# BatteryVCsmooth.net
KiCad netlist of a schematic drawn in Altium Designer
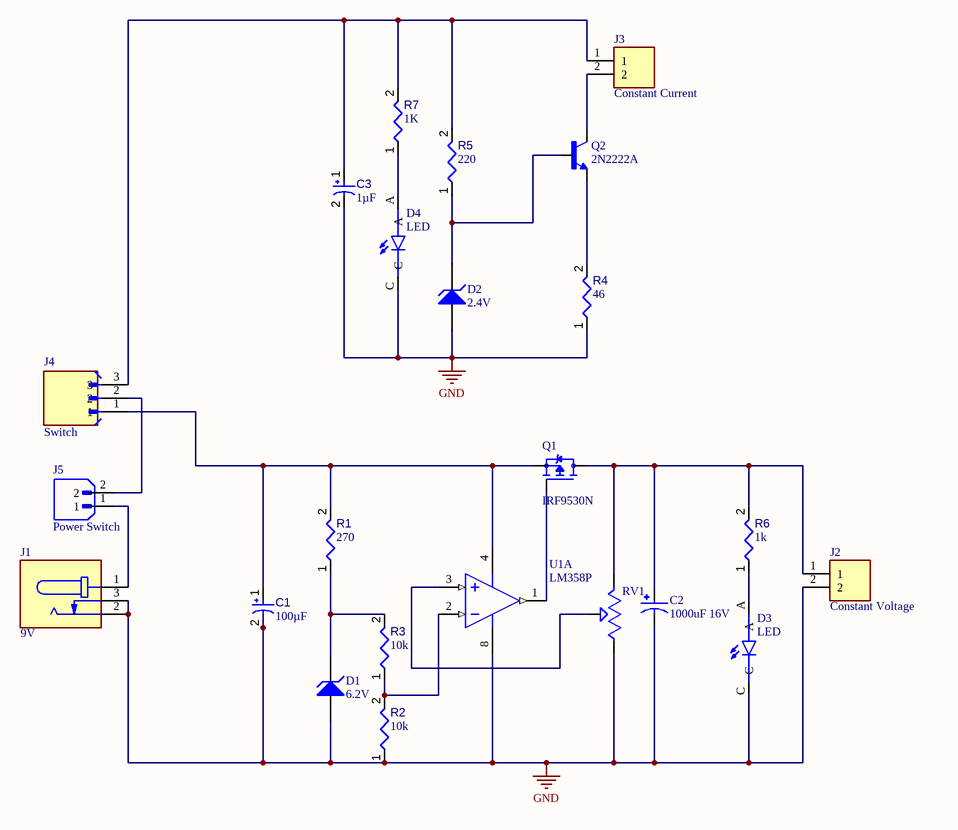
[diagram p0: BatteryVCsmooth.SchDoc]

(export (version "E")
  (design (tool "Eeschema 10.0.6"))
  (components
    (comp (ref "C1")
      (value "100µF")
      (footprint "CAPPR65-350-1150X800X1250")
      (description "Aluminum Electrolytic Capacitor, 100 uF, +/- 20%, 50 V, -40 to 85 degC, 2-Pin THD, RoHS, Bulk")
      (fields (field (name "MANUFACTURER") "Panasonic") (field (name "TOLERANCE") "20%"))
      (libsource (lib "GuardianCall") (part "CAP-P-2"))
    )
    (comp (ref "C2")
      (value "1000uF 16V")
      (footprint "CAPPRD500W60D1000H2000")
      (description "1000F 16V Aluminum Electrolytic Capacitors Radial, Can 10000 Hrs @ 105C")
      (fields (field (name "MP") "EEU-EB1C102B") (field (name "MF") "Panasonic"))
      (libsource (lib "1000uf_16V") (part "EEUEB1C102B"))
    )
    (comp (ref "C3")
      (value "1µF")
      (footprint "CAPPR55-200-1100X500X1200")
      (description "Aluminum Electrolytic Capacitor, 1 uF, +/- 20%, 50 V, -55 to 105 degC, 2-Pin THD, RoHS, Bulk")
      (fields (field (name "TOLERANCE") "20%") (field (name "MANUFACTURER") "Panasonic"))
      (libsource (lib "GuardianCall") (part "CAP-P-2"))
    )
    (comp (ref "D1")
      (value "6.2V")
      (footprint "FAIR-DO-35-2")
      (description "Zener Diode, 6.1 V, 5 mA, -65 to 200 degC, 2-Pin DO-35, RoHS, Bulk")
      (fields (field (name "MANUFACTURER") "Fairchild Semiconductor") (field (name "TOLERANCE") "6%"))
      (libsource (lib "GuardianCall") (part "DZEN-AK-2"))
    )
    (comp (ref "D2")
      (value "2.4V")
      (footprint "FAIR-DO-35-2")
      (description "Zener Diode, 2.4 V, 5 mA, -65 to 200 degC, 2-Pin DO-35, RoHS, Bulk")
      (fields (field (name "MANUFACTURER") "Fairchild Semiconductor") (field (name "TOLERANCE") "6%"))
      (libsource (lib "GuardianCall") (part "DZEN-AK-2"))
    )
    (comp (ref "D3")
      (value "LED")
      (footprint "LED_WP7113ID")
      (description "Red 617nm LED Indication - Discrete 2V Radial")
      (fields (field (name "MP") "WP7113ID") (field (name "MF") "Kingbright"))
      (libsource (lib "RedLED") (part "WP7113ID"))
    )
    (comp (ref "D4")
      (value "LED")
      (footprint "LED_WP7113ID")
      (description "Red 617nm LED Indication - Discrete 2V Radial")
      (fields (field (name "MP") "WP7113ID") (field (name "MF") "Kingbright"))
      (libsource (lib "RedLED") (part "WP7113ID"))
    )
    (comp (ref "J1")
      (value "9V")
      (footprint "CUI_PJ-035C")
      (fields (field (name "MF") "{'manufacturer': u'CUI Devices'}") (field (name "MP") "PJ-035C"))
      (libsource (lib "DCjack") (part "PJ-035C"))
    )
    (comp (ref "J2")
      (value "Constant Voltage")
      (footprint "TE_282841-2")
      (description "Conn Terminal Block 2 POS 5.08mm Solder ST Thru-Hole 17.5A/Contact")
      (fields (field (name "MP") "282841-2") (field (name "MF") "TE Connectivity"))
      (libsource (lib "Terminal Block Connector") (part "282841-2"))
    )
    (comp (ref "J3")
      (value "Constant Current")
      (footprint "TE_282841-2")
      (description "Conn Terminal Block 2 POS 5.08mm Solder ST Thru-Hole 17.5A/Contact")
      (fields (field (name "MP") "282841-2") (field (name "MF") "TE Connectivity"))
      (libsource (lib "Terminal Block Connector") (part "282841-2"))
    )
    (comp (ref "J4")
      (value "Switch")
      (footprint "JST_B3B-PH-K-S")
      (fields
        (field (name "MF") "{'manufacturer': u'JST Sales America Inc.'}")
        (field (name "MP") "B3B-PH-K-S")
      )
      (libsource (lib "JST3pin") (part "B3B-PH-K-S"))
    )
    (comp (ref "J5")
      (value "Power Switch")
      (footprint "JST_B2B-XH-A(LF)(SN)")
      (description "Connector Header Through Hole 2 position 0.098 (2.50mm)")
      (fields (field (name "MF") "JST Sales America Inc.") (field (name "MP") "B2B-XH-A(LF)(SN)"))
      (libsource (lib "B2B-XH-A_LF__SN_") (part "B2B-XH-A(LF)(SN)"))
    )
    (comp (ref "Q1")
      (value "IRF9530N")
      (footprint "TO220V")
      (description "Canal P 100 V 14A (Tc) 79W (Tc) Orificio pasante TO-220AB")
      (fields (field (name "MF") "Infineon") (field (name "DIGI-KEY_PART_NUMBER") "IRF9530NPBF-ND"))
      (libsource (lib "IRF9530NPBF") (part "IRF9530NPBF"))
    )
    (comp (ref "Q2")
      (value "2N2222A")
      (footprint "TO92254P470H750-3")
      (description "Bipolar (BJT) Transistor NPN 40 V 600 mA 250MHz 625 mW Through Hole TO-92")
      (fields (field (name "MF") "Diotec Semiconductor"))
      (libsource (lib "2N2222A NPN") (part "2N2222A"))
    )
    (comp (ref "R1")
      (value "270")
      (footprint "RESA60-630X240")
      (description "Axial Resistor, 270Ohm, +/- 1%, 0.25 W, -55 to 155 degC, 2-Pin THD, RoHS, Bulk")
      (fields (field (name "POWER") "250mW") (field (name "MANUFACTURER") "Yageo"))
      (libsource (lib "GuardianCall") (part "RES-2"))
    )
    (comp (ref "R2")
      (value "10k")
      (footprint "RESA60-630X240")
      (description "Axial Resistor, 10kOhm, +/- 1%, 0.25 W, -55 to 155 degC, 2-Pin THD, RoHS, Bulk")
      (fields (field (name "POWER") "250mW") (field (name "MANUFACTURER") "Yageo"))
      (libsource (lib "GuardianCall") (part "RES-2"))
    )
    (comp (ref "R3")
      (value "10k")
      (footprint "RESA60-630X240")
      (description "Axial Resistor, 10kOhm, +/- 1%, 0.25 W, -55 to 155 degC, 2-Pin THD, RoHS, Bulk")
      (fields (field (name "POWER") "250mW") (field (name "MANUFACTURER") "Yageo"))
      (libsource (lib "GuardianCall") (part "RES-2"))
    )
    (comp (ref "R4")
      (value "46")
      (footprint "RESA60-630X240")
      (description "Axial Resistor, 46Ohm, +/- 1%, 0.25 W, -55 to 155 degC, 2-Pin THD, RoHS, Bulk")
      (fields (field (name "POWER") "250mW") (field (name "MANUFACTURER") "Yageo"))
      (libsource (lib "GuardianCall") (part "RES-2"))
    )
    (comp (ref "R5")
      (value "220")
      (footprint "RESA60-630X240")
      (description "Axial Resistor, 220Ohm, +/- 1%, 0.25 W, -55 to 155 degC, 2-Pin THD, RoHS, Bulk")
      (fields (field (name "POWER") "250mW") (field (name "MANUFACTURER") "Yageo"))
      (libsource (lib "GuardianCall") (part "RES-2"))
    )
    (comp (ref "R6")
      (value "1k")
      (footprint "RESA60-630X240")
      (description "Axial Resistor, 1kOhm, +/- 1%, 0.25 W, -55 to 155 degC, 2-Pin THD, RoHS, Bulk")
      (fields (field (name "POWER") "250mW") (field (name "MANUFACTURER") "Yageo"))
      (libsource (lib "GuardianCall") (part "RES-2"))
    )
    (comp (ref "R7")
      (value "1K")
      (footprint "RESA60-630X240")
      (description "Axial Resistor, 1kOhm, +/- 1%, 0.25 W, -55 to 155 degC, 2-Pin THD, RoHS, Bulk")
      (fields (field (name "POWER") "250mW") (field (name "MANUFACTURER") "Yageo"))
      (libsource (lib "GuardianCall") (part "RES-2"))
    )
    (comp (ref "RV1")
      (value "~")
      (footprint "TRIM_PV36W254C01B00")
      (description "100 kOhms 0.5W, 1/2W PC Pins Through Hole Trimmer Potentiometer Cermet 25.0 Turn Top Adjustment")
      (fields (field (name "MF") "Bourns") (field (name "MP") "PV36W254C01B00"))
      (libsource (lib "PV36W254C01B00") (part "PV36W254C01B00"))
    )
    (comp (ref "U1")
      (value "LM358P")
      (footprint "P0008A")
      (description "Dual Operational Amplifier, 3 to 32 V, 0 to 70 degC, 8-Pin PDIP (P), Pb-Free (RoHS), Tube")
      (fields (field (name "MANUFACTURER") "Texas Instruments (TI)"))
      (libsource (lib "GuardianCall") (part "TI-LM358-8"))
    )
  )
  (nets
    (net (code "1") (name "GND") (class "Default")
      (node (ref "C1") (pin "2") (pinfunction "2_2") (pintype "passive"))
      (node (ref "C2") (pin "N") (pinfunction "N_N") (pintype "passive"))
      (node (ref "C3") (pin "2") (pinfunction "2_2") (pintype "passive"))
      (node (ref "D1") (pin "1") (pinfunction "A_1") (pintype "passive"))
      (node (ref "D2") (pin "1") (pinfunction "A_1") (pintype "passive"))
      (node (ref "D3") (pin "C") (pinfunction "C_C") (pintype "passive"))
      (node (ref "D4") (pin "C") (pinfunction "C_C") (pintype "passive"))
      (node (ref "J1") (pin "2") (pinfunction "2_2") (pintype "passive"))
      (node (ref "J1") (pin "3") (pinfunction "3_3") (pintype "passive"))
      (node (ref "J2") (pin "2") (pinfunction "2_2") (pintype "passive"))
      (node (ref "R2") (pin "1") (pinfunction "1_1") (pintype "passive"))
      (node (ref "R4") (pin "1") (pinfunction "1_1") (pintype "passive"))
      (node (ref "RV1") (pin "1") (pinfunction "1_1") (pintype "passive"))
      (node (ref "U1") (pin "8") (pinfunction "VCC_8") (pintype "power_in"))
    )
    (net (code "2") (name "Net-(C3-Pad1)") (class "Default")
      (node (ref "C3") (pin "1") (pinfunction "1_1") (pintype "passive"))
      (node (ref "J3") (pin "1") (pinfunction "1_1") (pintype "passive"))
      (node (ref "J4") (pin "3") (pinfunction "3_3") (pintype "passive"))
      (node (ref "R5") (pin "2") (pinfunction "2_2") (pintype "passive"))
      (node (ref "R7") (pin "2") (pinfunction "2_2") (pintype "passive"))
    )
    (net (code "3") (name "Net-(D1-K)") (class "Default")
      (node (ref "D1") (pin "2") (pinfunction "K_2") (pintype "passive"))
      (node (ref "R1") (pin "1") (pinfunction "1_1") (pintype "passive"))
      (node (ref "R3") (pin "2") (pinfunction "2_2") (pintype "passive"))
    )
    (net (code "4") (name "Net-(D2-K)") (class "Default")
      (node (ref "D2") (pin "2") (pinfunction "K_2") (pintype "passive"))
      (node (ref "Q2") (pin "2") (pinfunction "B_2") (pintype "passive"))
      (node (ref "R5") (pin "1") (pinfunction "1_1") (pintype "passive"))
    )
    (net (code "5") (name "Net-(D3-PadA)") (class "Default")
      (node (ref "D3") (pin "A") (pinfunction "A_A") (pintype "passive"))
      (node (ref "R6") (pin "1") (pinfunction "1_1") (pintype "passive"))
    )
    (net (code "6") (name "Net-(D4-PadA)") (class "Default")
      (node (ref "D4") (pin "A") (pinfunction "A_A") (pintype "passive"))
      (node (ref "R7") (pin "1") (pinfunction "1_1") (pintype "passive"))
    )
    (net (code "7") (name "Net-(J1-Pad1)") (class "Default")
      (node (ref "J1") (pin "1") (pinfunction "1_1") (pintype "passive"))
      (node (ref "J5") (pin "1") (pinfunction "1_1") (pintype "passive"))
    )
    (net (code "8") (name "Net-(J4-Pad2)") (class "Default")
      (node (ref "J4") (pin "2") (pinfunction "2_2") (pintype "passive"))
      (node (ref "J5") (pin "2") (pinfunction "2_2") (pintype "passive"))
    )
    (net (code "9") (name "Net-(Q1-D)") (class "Default")
      (node (ref "C2") (pin "P") (pinfunction "P_P") (pintype "passive"))
      (node (ref "J2") (pin "1") (pinfunction "1_1") (pintype "passive"))
      (node (ref "Q1") (pin "2") (pinfunction "D_2") (pintype "passive"))
      (node (ref "R6") (pin "2") (pinfunction "2_2") (pintype "passive"))
      (node (ref "RV1") (pin "3") (pinfunction "3_3") (pintype "passive"))
    )
    (net (code "10") (name "Net-(Q1-G)") (class "Default")
      (node (ref "Q1") (pin "1") (pinfunction "G_1") (pintype "passive"))
      (node (ref "U1") (pin "1") (pinfunction "1OUT_1") (pintype "output"))
    )
    (net (code "11") (name "Net-(Q1-S)") (class "Default")
      (node (ref "C1") (pin "1") (pinfunction "1_1") (pintype "passive"))
      (node (ref "J4") (pin "1") (pinfunction "1_1") (pintype "passive"))
      (node (ref "Q1") (pin "3") (pinfunction "S_3") (pintype "passive"))
      (node (ref "R1") (pin "2") (pinfunction "2_2") (pintype "passive"))
      (node (ref "U1") (pin "4") (pinfunction "GND_4") (pintype "power_in"))
    )
    (net (code "12") (name "Net-(Q2-C)") (class "Default")
      (node (ref "J3") (pin "2") (pinfunction "2_2") (pintype "passive"))
      (node (ref "Q2") (pin "3") (pinfunction "C_3") (pintype "passive"))
    )
    (net (code "13") (name "Net-(Q2-E)") (class "Default")
      (node (ref "Q2") (pin "1") (pinfunction "E_1") (pintype "passive"))
      (node (ref "R4") (pin "2") (pinfunction "2_2") (pintype "passive"))
    )
    (net (code "14") (name "Net-(U1A-1IN+)") (class "Default")
      (node (ref "RV1") (pin "2") (pinfunction "2_2") (pintype "passive"))
      (node (ref "U1") (pin "3") (pinfunction "1IN+_3") (pintype "input"))
    )
    (net (code "15") (name "Net-(U1A-1IN-)") (class "Default")
      (node (ref "R2") (pin "2") (pinfunction "2_2") (pintype "passive"))
      (node (ref "R3") (pin "1") (pinfunction "1_1") (pintype "passive"))
      (node (ref "U1") (pin "2") (pinfunction "1IN-_2") (pintype "input"))
    )
  )
)
